# schematics.net
KiCad netlist of a schematic drawn in Altium Designer
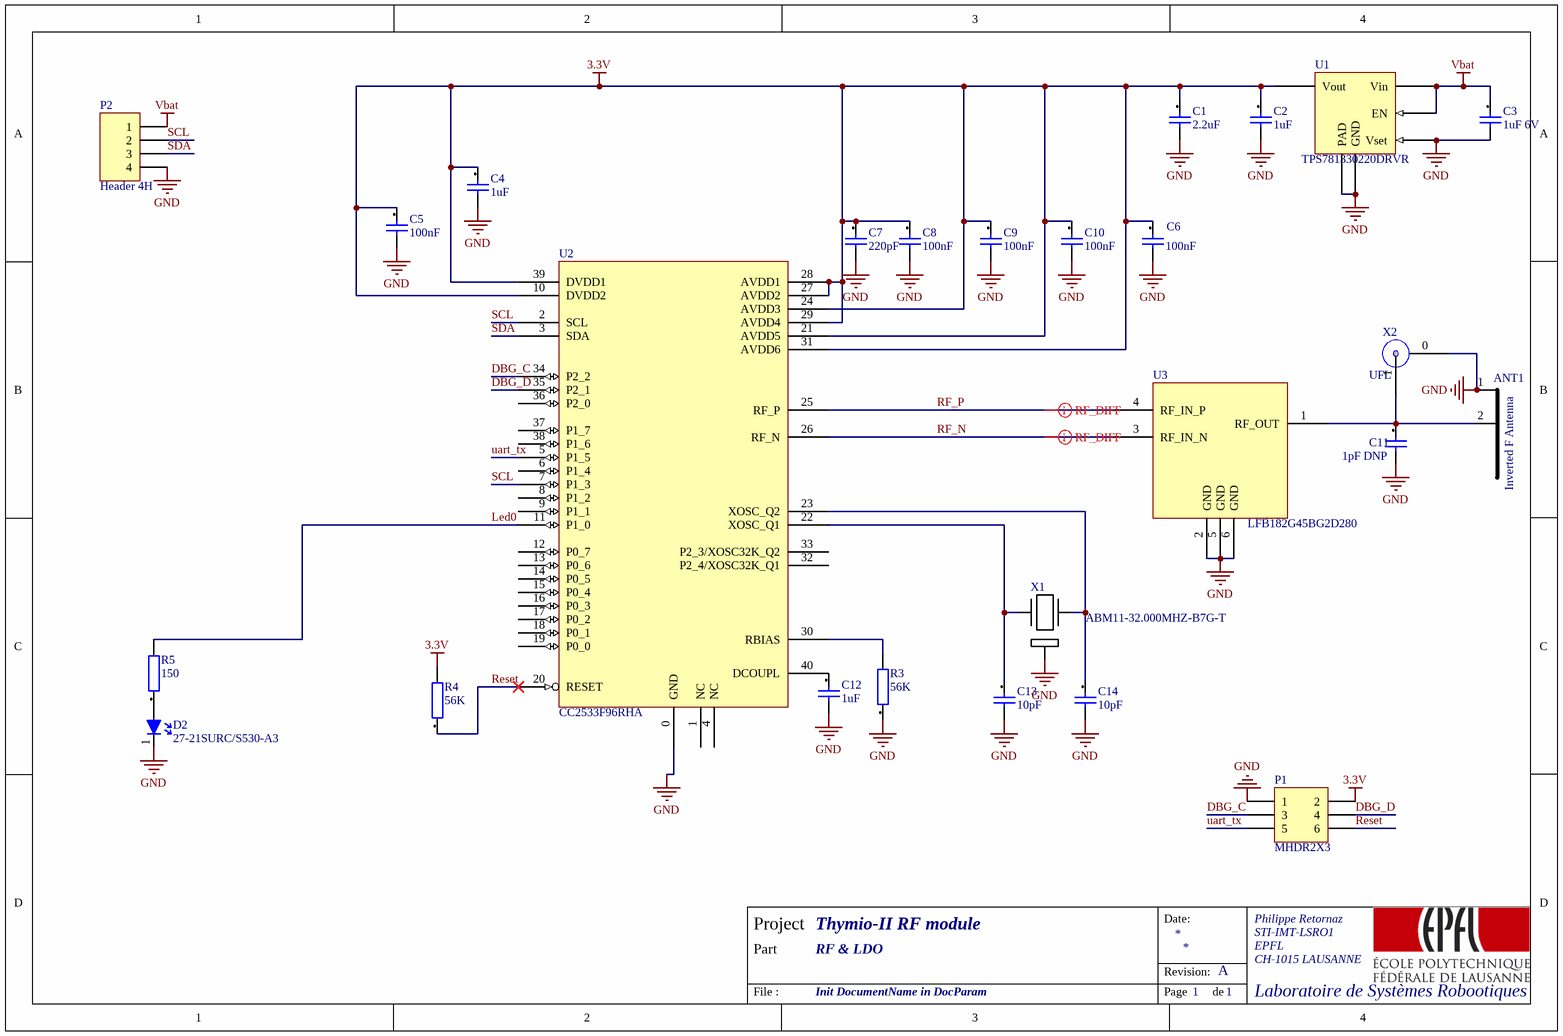
[diagram p0: schematics.SchDoc]

(export (version "E")
  (design (tool "Eeschema 10.0.6"))
  (components
    (comp (ref "ANT1")
      (value "Inverted F Antenna")
      (footprint "IFA_2")
      (libsource (lib "cc253x") (part "PIF_Antenna"))
    )
    (comp (ref "C1")
      (value "2.2uF")
      (footprint "CAPC1005X05L")
      (description "Capacitor")
      (fields (field (name "MANUFACTURER") "Epcos") (field (name "VOLTAGE") "25"))
      (libsource (lib "LSRO1Altium") (part "CAP-NP"))
    )
    (comp (ref "C2")
      (value "1uF")
      (footprint "CAPC1005X05L")
      (description "Capacitor")
      (fields (field (name "MANUFACTURER") "Kemet") (field (name "VOLTAGE") "6.3"))
      (libsource (lib "LSRO1Altium") (part "CAP-NP"))
    )
    (comp (ref "C3")
      (value "1uF 6V")
      (footprint "CAPC1005X05L")
      (description "Capacitor")
      (fields (field (name "MANUFACTURER") "Kemet") (field (name "VOLTAGE") "6.3"))
      (libsource (lib "LSRO1Altium") (part "CAP-NP"))
    )
    (comp (ref "C4")
      (value "1uF")
      (footprint "CAPC1005X05L")
      (description "Capacitor")
      (fields (field (name "MANUFACTURER") "Kemet") (field (name "VOLTAGE") "6.3"))
      (libsource (lib "LSRO1Altium") (part "CAP-NP"))
    )
    (comp (ref "C5")
      (value "100nF")
      (footprint "CAPC1005X05L")
      (description "Capacitor")
      (fields (field (name "MANUFACTURER") "Kemet") (field (name "VOLTAGE") "16"))
      (libsource (lib "LSRO1Altium") (part "CAP-NP"))
    )
    (comp (ref "C6")
      (value "100nF")
      (footprint "CAPC1005X05L")
      (description "Capacitor")
      (fields (field (name "MANUFACTURER") "Kemet") (field (name "VOLTAGE") "16"))
      (libsource (lib "LSRO1Altium") (part "CAP-NP"))
    )
    (comp (ref "C7")
      (value "220pF")
      (footprint "CAPC1005X05L")
      (description "Capacitor")
      (fields (field (name "MANUFACTURER") "Kemet") (field (name "VOLTAGE") "16"))
      (libsource (lib "LSRO1Altium") (part "CAP-NP"))
    )
    (comp (ref "C8")
      (value "100nF")
      (footprint "CAPC1005X05L")
      (description "Capacitor")
      (fields (field (name "MANUFACTURER") "Kemet") (field (name "VOLTAGE") "16"))
      (libsource (lib "LSRO1Altium") (part "CAP-NP"))
    )
    (comp (ref "C9")
      (value "100nF")
      (footprint "CAPC1005X05L")
      (description "Capacitor")
      (fields (field (name "MANUFACTURER") "Kemet") (field (name "VOLTAGE") "16"))
      (libsource (lib "LSRO1Altium") (part "CAP-NP"))
    )
    (comp (ref "C10")
      (value "100nF")
      (footprint "CAPC1005X05L")
      (description "Capacitor")
      (fields (field (name "MANUFACTURER") "Kemet") (field (name "VOLTAGE") "16"))
      (libsource (lib "LSRO1Altium") (part "CAP-NP"))
    )
    (comp (ref "C11")
      (value "1pF DNP")
      (footprint "CAPC1005X05L")
      (description "Capacitor")
      (fields (field (name "MANUFACTURER") "Murata") (field (name "VOLTAGE") "50"))
      (libsource (lib "LSRO1Altium") (part "CAP-NP"))
    )
    (comp (ref "C12")
      (value "1uF")
      (footprint "CAPC1005X05L")
      (description "Capacitor")
      (fields (field (name "MANUFACTURER") "Kemet") (field (name "VOLTAGE") "6.3"))
      (libsource (lib "LSRO1Altium") (part "CAP-NP"))
    )
    (comp (ref "C13")
      (value "10pF")
      (footprint "CAPC1005X05L")
      (description "Capacitor")
      (fields (field (name "MANUFACTURER") "Murata") (field (name "VOLTAGE") "50"))
      (libsource (lib "LSRO1Altium") (part "CAP-NP"))
    )
    (comp (ref "C14")
      (value "10pF")
      (footprint "CAPC1005X05L")
      (description "Capacitor")
      (fields (field (name "MANUFACTURER") "Murata") (field (name "VOLTAGE") "50"))
      (libsource (lib "LSRO1Altium") (part "CAP-NP"))
    )
    (comp (ref "D2")
      (value "27-21SURC/S530-A3")
      (footprint "cc253x:Led-side")
      (description "SMD Red led right angle mount 2V@20ma 57mcd")
      (fields (field (name "VERIFIEDCOMMENT") "ToDo"))
      (libsource (lib "LEDs") (part "LED"))
    )
    (comp (ref "P1")
      (value "MHDR2X3")
      (footprint "MHDR2X3")
      (description "Header, 3-Pin, Dual row")
      (fields (field (name "PUBLISHER") "Altium Limited"))
      (libsource (lib "Miscellaneous Connectors") (part "MHDR2X3"))
    )
    (comp (ref "P2")
      (value "Header 4H")
      (footprint "HDR1X4H")
      (description "Header, 4-Pin, Right Angle")
      (fields (field (name "PUBLISHER") "Altium Limited"))
      (libsource (lib "Miscellaneous Connectors") (part "Header 4H"))
    )
    (comp (ref "R3")
      (value "56K")
      (footprint "RESC1005X04L")
      (description "Resistor")
      (fields (field (name "TOLERANCE") "+/-1") (field (name "MANUFACTURER") "Phycomp"))
      (libsource (lib "LSRO1Altium") (part "RES"))
    )
    (comp (ref "R4")
      (value "56K")
      (footprint "RESC1005X04L")
      (description "Resistor")
      (fields (field (name "TOLERANCE") "+/-1") (field (name "MANUFACTURER") "Phycomp"))
      (libsource (lib "LSRO1Altium") (part "RES"))
    )
    (comp (ref "R5")
      (value "150")
      (footprint "RESC1005X04L")
      (description "Resistor")
      (fields (field (name "TOLERANCE") "+/-1") (field (name "MANUFACTURER") "Phycomp"))
      (libsource (lib "LSRO1Altium") (part "RES"))
    )
    (comp (ref "U1")
      (value "TPS781330220DRVR")
      (footprint "QFN65P200X200X80-6N")
      (description "150mA LDO TI")
      (libsource (lib "cc253x") (part "TPS781"))
    )
    (comp (ref "U2")
      (value "CC2533F96RHA")
      (footprint "QFN50P600X600X100-40L-2")
      (description "A True System-on-Chip Solution for 2.4-GHz IEEE 802.15.4")
      (libsource (lib "cc253x") (part "cc2533"))
    )
    (comp (ref "U3")
      (value "LFB182G45BG2D280")
      (footprint "LFB182G45BG2D280")
      (description "Balun for CC253x")
      (libsource (lib "cc253x") (part "2450BM15A0002"))
    )
    (comp (ref "X1")
      (value "ABM11-32.000MHZ-B7G-T")
      (footprint "Abracon-ABM11")
      (description "32Mhz Crystal, 15ppm")
      (libsource (lib "cc253x") (part "ABM11-32.000MHZ-B7G-T"))
    )
    (comp (ref "X2")
      (value "UFL")
      (footprint "U.FL-R-SMT-1")
      (libsource (lib "cc253x") (part "U.FL-R-SMT-1"))
    )
  )
  (nets
    (net (code "1") (name "/DBG_C") (class "Default")
      (node (ref "P1") (pin "3") (pinfunction "3_3") (pintype "passive"))
      (node (ref "U2") (pin "34") (pinfunction "P2_2_34") (pintype "bidirectional"))
    )
    (net (code "2") (name "/DBG_D") (class "Default")
      (node (ref "P1") (pin "4") (pinfunction "4_4") (pintype "passive"))
      (node (ref "U2") (pin "35") (pinfunction "P2_1_35") (pintype "bidirectional"))
    )
    (net (code "3") (name "/Led0") (class "Default")
      (node (ref "R5") (pin "2") (pinfunction "2_2") (pintype "passive"))
      (node (ref "U2") (pin "11") (pinfunction "P1_0_11") (pintype "bidirectional"))
    )
    (net (code "4") (name "/RF_N") (class "Default")
      (node (ref "U2") (pin "26") (pinfunction "RF_N_26") (pintype "passive"))
      (node (ref "U3") (pin "3") (pinfunction "RF_IN_N_3") (pintype "passive"))
    )
    (net (code "5") (name "/RF_P") (class "Default")
      (node (ref "U2") (pin "25") (pinfunction "RF_P_25") (pintype "passive"))
      (node (ref "U3") (pin "4") (pinfunction "RF_IN_P_4") (pintype "passive"))
    )
    (net (code "6") (name "/Reset") (class "Default")
      (node (ref "P1") (pin "6") (pinfunction "6_6") (pintype "passive"))
      (node (ref "R4") (pin "1") (pinfunction "1_1") (pintype "passive"))
      (node (ref "U2") (pin "20") (pinfunction "RESET_20") (pintype "input"))
    )
    (net (code "7") (name "/SCL") (class "Default")
      (node (ref "P2") (pin "2") (pinfunction "2_2") (pintype "passive"))
      (node (ref "U2") (pin "2") (pinfunction "SCL_2") (pintype "open_collector"))
      (node (ref "U2") (pin "7") (pinfunction "P1_3_7") (pintype "bidirectional"))
    )
    (net (code "8") (name "/SDA") (class "Default")
      (node (ref "P2") (pin "3") (pinfunction "3_3") (pintype "passive"))
      (node (ref "U2") (pin "3") (pinfunction "SDA_3") (pintype "open_collector"))
    )
    (net (code "9") (name "/uart_tx") (class "Default")
      (node (ref "P1") (pin "5") (pinfunction "5_5") (pintype "passive"))
      (node (ref "U2") (pin "5") (pinfunction "P1_5_5") (pintype "bidirectional"))
    )
    (net (code "10") (name "3.3V") (class "Default")
      (node (ref "C1") (pin "1") (pinfunction "1_1") (pintype "passive"))
      (node (ref "C10") (pin "1") (pinfunction "1_1") (pintype "passive"))
      (node (ref "C2") (pin "1") (pinfunction "1_1") (pintype "passive"))
      (node (ref "C4") (pin "1") (pinfunction "1_1") (pintype "passive"))
      (node (ref "C5") (pin "1") (pinfunction "1_1") (pintype "passive"))
      (node (ref "C6") (pin "1") (pinfunction "1_1") (pintype "passive"))
      (node (ref "C7") (pin "1") (pinfunction "1_1") (pintype "passive"))
      (node (ref "C8") (pin "1") (pinfunction "1_1") (pintype "passive"))
      (node (ref "C9") (pin "1") (pinfunction "1_1") (pintype "passive"))
      (node (ref "P1") (pin "2") (pinfunction "2_2") (pintype "passive"))
      (node (ref "R4") (pin "2") (pinfunction "2_2") (pintype "passive"))
      (node (ref "U1") (pin "5") (pinfunction "Vout_5") (pintype "power_in"))
      (node (ref "U2") (pin "10") (pinfunction "DVDD2_10") (pintype "power_in"))
      (node (ref "U2") (pin "21") (pinfunction "AVDD5_21") (pintype "power_in"))
      (node (ref "U2") (pin "24") (pinfunction "AVDD3_24") (pintype "power_in"))
      (node (ref "U2") (pin "27") (pinfunction "AVDD2_27") (pintype "power_in"))
      (node (ref "U2") (pin "28") (pinfunction "AVDD1_28") (pintype "power_in"))
      (node (ref "U2") (pin "29") (pinfunction "AVDD4_29") (pintype "power_in"))
      (node (ref "U2") (pin "31") (pinfunction "AVDD6_31") (pintype "power_in"))
      (node (ref "U2") (pin "39") (pinfunction "DVDD1_39") (pintype "power_in"))
    )
    (net (code "11") (name "GND") (class "Default")
      (node (ref "ANT1") (pin "1") (pinfunction "GND_1") (pintype "passive"))
      (node (ref "C1") (pin "2") (pinfunction "2_2") (pintype "passive"))
      (node (ref "C10") (pin "2") (pinfunction "2_2") (pintype "passive"))
      (node (ref "C11") (pin "2") (pinfunction "2_2") (pintype "passive"))
      (node (ref "C12") (pin "2") (pinfunction "2_2") (pintype "passive"))
      (node (ref "C13") (pin "2") (pinfunction "2_2") (pintype "passive"))
      (node (ref "C14") (pin "2") (pinfunction "2_2") (pintype "passive"))
      (node (ref "C2") (pin "2") (pinfunction "2_2") (pintype "passive"))
      (node (ref "C3") (pin "2") (pinfunction "2_2") (pintype "passive"))
      (node (ref "C4") (pin "2") (pinfunction "2_2") (pintype "passive"))
      (node (ref "C5") (pin "2") (pinfunction "2_2") (pintype "passive"))
      (node (ref "C6") (pin "2") (pinfunction "2_2") (pintype "passive"))
      (node (ref "C7") (pin "2") (pinfunction "2_2") (pintype "passive"))
      (node (ref "C8") (pin "2") (pinfunction "2_2") (pintype "passive"))
      (node (ref "C9") (pin "2") (pinfunction "2_2") (pintype "passive"))
      (node (ref "D2") (pin "1") (pinfunction "K_1") (pintype "passive"))
      (node (ref "P1") (pin "1") (pinfunction "1_1") (pintype "passive"))
      (node (ref "P2") (pin "4") (pinfunction "4_4") (pintype "passive"))
      (node (ref "R3") (pin "1") (pinfunction "1_1") (pintype "passive"))
      (node (ref "U1") (pin "3") (pinfunction "Vset_3") (pintype "input"))
      (node (ref "U1") (pin "4") (pinfunction "GND_4") (pintype "power_in"))
      (node (ref "U1") (pin "7") (pinfunction "PAD_7") (pintype "passive"))
      (node (ref "U2") (pin "0") (pinfunction "GND_0") (pintype "power_in"))
      (node (ref "U3") (pin "2") (pinfunction "GND_2") (pintype "passive"))
      (node (ref "U3") (pin "5") (pinfunction "GND_5") (pintype "passive"))
      (node (ref "U3") (pin "6") (pinfunction "GND_6") (pintype "passive"))
      (node (ref "X1") (pin "0") (pinfunction "GND_0") (pintype "power_in"))
      (node (ref "X2") (pin "0") (pinfunction "NC_0") (pintype "power_in"))
    )
    (net (code "12") (name "Net-(ANT1-Input)") (class "Default")
      (node (ref "ANT1") (pin "2") (pinfunction "Input_2") (pintype "passive"))
      (node (ref "C11") (pin "1") (pinfunction "1_1") (pintype "passive"))
      (node (ref "U3") (pin "1") (pinfunction "RF_OUT_1") (pintype "passive"))
      (node (ref "X2") (pin "1") (pinfunction "1_1") (pintype "passive"))
    )
    (net (code "13") (name "Net-(D2-A)") (class "Default")
      (node (ref "D2") (pin "2") (pinfunction "A_2") (pintype "passive"))
      (node (ref "R5") (pin "1") (pinfunction "1_1") (pintype "passive"))
    )
    (net (code "14") (name "Net-(U2-DCOUPL)") (class "Default")
      (node (ref "C12") (pin "1") (pinfunction "1_1") (pintype "passive"))
      (node (ref "U2") (pin "40") (pinfunction "DCOUPL_40") (pintype "passive"))
    )
    (net (code "15") (name "Net-(U2-RBIAS)") (class "Default")
      (node (ref "R3") (pin "2") (pinfunction "2_2") (pintype "passive"))
      (node (ref "U2") (pin "30") (pinfunction "RBIAS_30") (pintype "passive"))
    )
    (net (code "16") (name "Net-(U2-XOSC_Q1)") (class "Default")
      (node (ref "C13") (pin "1") (pinfunction "1_1") (pintype "passive"))
      (node (ref "U2") (pin "22") (pinfunction "XOSC_Q1_22") (pintype "passive"))
      (node (ref "X1") (pin "1") (pinfunction "1_1") (pintype "power_in"))
    )
    (net (code "17") (name "Net-(U2-XOSC_Q2)") (class "Default")
      (node (ref "C14") (pin "1") (pinfunction "1_1") (pintype "passive"))
      (node (ref "U2") (pin "23") (pinfunction "XOSC_Q2_23") (pintype "passive"))
      (node (ref "X1") (pin "2") (pinfunction "2_2") (pintype "power_in"))
    )
    (net (code "18") (name "Vbat") (class "Default")
      (node (ref "C3") (pin "1") (pinfunction "1_1") (pintype "passive"))
      (node (ref "P2") (pin "1") (pinfunction "1_1") (pintype "passive"))
      (node (ref "U1") (pin "1") (pinfunction "Vin_1") (pintype "power_in"))
      (node (ref "U1") (pin "2") (pinfunction "EN_2") (pintype "input"))
    )
    (net (code "19") (name "unconnected-(U2-NC-Pad1)") (class "Default")
      (node (ref "U2") (pin "1") (pinfunction "NC_1") (pintype "passive"))
    )
    (net (code "20") (name "unconnected-(U2-NC-Pad4)") (class "Default")
      (node (ref "U2") (pin "4") (pinfunction "NC_4") (pintype "passive"))
    )
    (net (code "21") (name "unconnected-(U2-P0_0-Pad19)") (class "Default")
      (node (ref "U2") (pin "19") (pinfunction "P0_0_19") (pintype "bidirectional"))
    )
    (net (code "22") (name "unconnected-(U2-P0_1-Pad18)") (class "Default")
      (node (ref "U2") (pin "18") (pinfunction "P0_1_18") (pintype "bidirectional"))
    )
    (net (code "23") (name "unconnected-(U2-P0_2-Pad17)") (class "Default")
      (node (ref "U2") (pin "17") (pinfunction "P0_2_17") (pintype "bidirectional"))
    )
    (net (code "24") (name "unconnected-(U2-P0_3-Pad16)") (class "Default")
      (node (ref "U2") (pin "16") (pinfunction "P0_3_16") (pintype "bidirectional"))
    )
    (net (code "25") (name "unconnected-(U2-P0_4-Pad15)") (class "Default")
      (node (ref "U2") (pin "15") (pinfunction "P0_4_15") (pintype "bidirectional"))
    )
    (net (code "26") (name "unconnected-(U2-P0_5-Pad14)") (class "Default")
      (node (ref "U2") (pin "14") (pinfunction "P0_5_14") (pintype "bidirectional"))
    )
    (net (code "27") (name "unconnected-(U2-P0_6-Pad13)") (class "Default")
      (node (ref "U2") (pin "13") (pinfunction "P0_6_13") (pintype "bidirectional"))
    )
    (net (code "28") (name "unconnected-(U2-P0_7-Pad12)") (class "Default")
      (node (ref "U2") (pin "12") (pinfunction "P0_7_12") (pintype "bidirectional"))
    )
    (net (code "29") (name "unconnected-(U2-P1_1-Pad9)") (class "Default")
      (node (ref "U2") (pin "9") (pinfunction "P1_1_9") (pintype "bidirectional"))
    )
    (net (code "30") (name "unconnected-(U2-P1_2-Pad8)") (class "Default")
      (node (ref "U2") (pin "8") (pinfunction "P1_2_8") (pintype "bidirectional"))
    )
    (net (code "31") (name "unconnected-(U2-P1_4-Pad6)") (class "Default")
      (node (ref "U2") (pin "6") (pinfunction "P1_4_6") (pintype "bidirectional"))
    )
    (net (code "32") (name "unconnected-(U2-P1_6-Pad38)") (class "Default")
      (node (ref "U2") (pin "38") (pinfunction "P1_6_38") (pintype "bidirectional"))
    )
    (net (code "33") (name "unconnected-(U2-P1_7-Pad37)") (class "Default")
      (node (ref "U2") (pin "37") (pinfunction "P1_7_37") (pintype "bidirectional"))
    )
    (net (code "34") (name "unconnected-(U2-P2_0-Pad36)") (class "Default")
      (node (ref "U2") (pin "36") (pinfunction "P2_0_36") (pintype "bidirectional"))
    )
    (net (code "35") (name "unconnected-(U2-P2_3{slash}XOSC32K_Q2-Pad33)") (class "Default")
      (node (ref "U2") (pin "33") (pinfunction "P2_3/XOSC32K_Q2_33") (pintype "passive"))
    )
    (net (code "36") (name "unconnected-(U2-P2_4{slash}XOSC32K_Q1-Pad32)") (class "Default")
      (node (ref "U2") (pin "32") (pinfunction "P2_4/XOSC32K_Q1_32") (pintype "passive"))
    )
  )
)
